# untitled.net
KiCad netlist of a schematic drawn in EAGLE
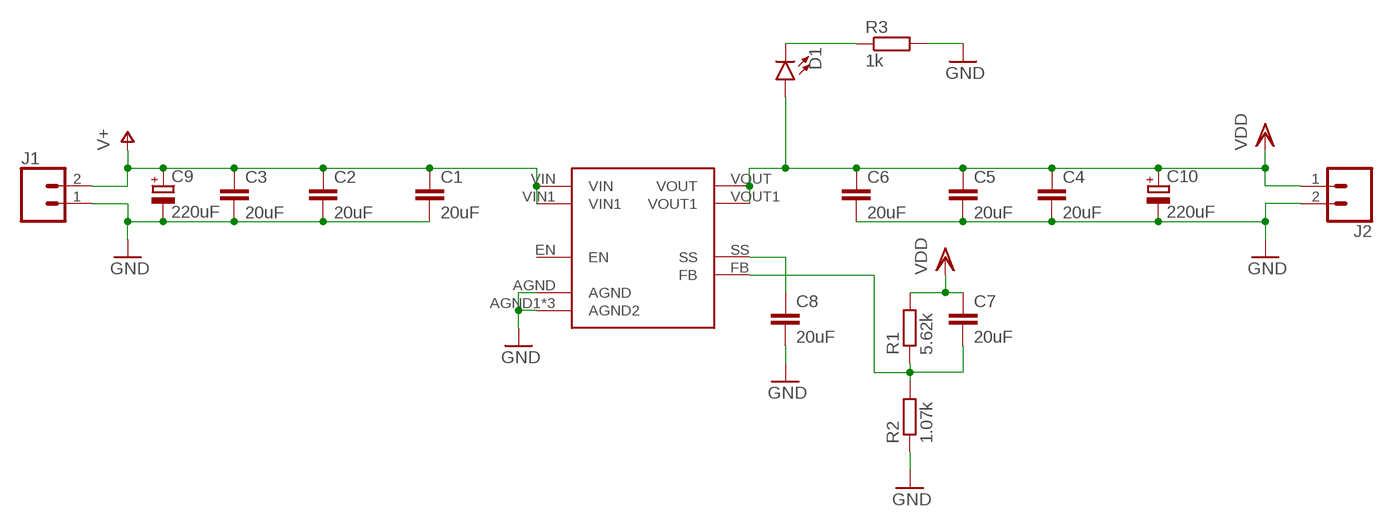
[diagram p0: schematic, sheet 1]

(export (version "E")
  (design (tool "Eeschema 10.0.6"))
  (components
    (comp (ref "C1")
      (value "20uF")
      (footprint "eagle-import:C0805K")
      (libsource (lib "eagle-import") (part "C-EUC0805K"))
    )
    (comp (ref "C2")
      (value "20uF")
      (footprint "eagle-import:C0805K")
      (libsource (lib "eagle-import") (part "C-EUC0805K"))
    )
    (comp (ref "C3")
      (value "20uF")
      (footprint "eagle-import:C0805K")
      (libsource (lib "eagle-import") (part "C-EUC0805K"))
    )
    (comp (ref "C4")
      (value "20uF")
      (footprint "eagle-import:C0805K")
      (libsource (lib "eagle-import") (part "C-EUC0805K"))
    )
    (comp (ref "C5")
      (value "20uF")
      (footprint "eagle-import:C0805K")
      (libsource (lib "eagle-import") (part "C-EUC0805K"))
    )
    (comp (ref "C6")
      (value "20uF")
      (footprint "eagle-import:C0805K")
      (libsource (lib "eagle-import") (part "C-EUC0805K"))
    )
    (comp (ref "C7")
      (value "20uF")
      (footprint "eagle-import:C0805K")
      (libsource (lib "eagle-import") (part "C-EUC0805K"))
    )
    (comp (ref "C8")
      (value "20uF")
      (footprint "eagle-import:C0805K")
      (libsource (lib "eagle-import") (part "C-EUC0805K"))
    )
    (comp (ref "C9")
      (value "220uF")
      (footprint "eagle-import:153CLV-0810")
      (libsource (lib "eagle-import") (part "CPOL-EU153CLV-0810"))
    )
    (comp (ref "C10")
      (value "220uF")
      (footprint "eagle-import:153CLV-0810")
      (libsource (lib "eagle-import") (part "CPOL-EU153CLV-0810"))
    )
    (comp (ref "D1")
      (value "LED5MM")
      (footprint "eagle-import:LED_5MM")
      (libsource (lib "eagle-import") (part "LED5MM"))
    )
    (comp (ref "J1")
      (value "CONN_025MM")
      (footprint "eagle-import:SCREWTERMINAL-5MM-2")
      (libsource (lib "eagle-import") (part "CONN_025MM"))
    )
    (comp (ref "J2")
      (value "CONN_025MM")
      (footprint "eagle-import:SCREWTERMINAL-5MM-2")
      (libsource (lib "eagle-import") (part "CONN_025MM"))
    )
    (comp (ref "R1")
      (value "5.62k")
      (footprint "eagle-import:R0805")
      (libsource (lib "eagle-import") (part "R-EU_R0805"))
    )
    (comp (ref "R2")
      (value "1.07k")
      (footprint "eagle-import:R0805")
      (libsource (lib "eagle-import") (part "R-EU_R0805"))
    )
    (comp (ref "R3")
      (value "1k")
      (footprint "eagle-import:R0805")
      (libsource (lib "eagle-import") (part "R-EU_R0805"))
    )
    (comp (ref "U$1")
      (value "LMZ13610")
      (footprint "eagle-import:LMZ13610")
      (libsource (lib "eagle-import") (part "LMZ13610"))
    )
  )
  (nets
    (net (code "1") (name "GND") (class "Default")
      (node (ref "C1") (pin "2") (pinfunction "2_2") (pintype "passive"))
      (node (ref "C10") (pin "-") (pinfunction "-_-") (pintype "passive"))
      (node (ref "C2") (pin "2") (pinfunction "2_2") (pintype "passive"))
      (node (ref "C3") (pin "2") (pinfunction "2_2") (pintype "passive"))
      (node (ref "C4") (pin "2") (pinfunction "2_2") (pintype "passive"))
      (node (ref "C5") (pin "2") (pinfunction "2_2") (pintype "passive"))
      (node (ref "C6") (pin "2") (pinfunction "2_2") (pintype "passive"))
      (node (ref "C8") (pin "2") (pinfunction "2_2") (pintype "passive"))
      (node (ref "C9") (pin "-") (pinfunction "-_-") (pintype "passive"))
      (node (ref "J1") (pin "1") (pinfunction "1_1") (pintype "passive"))
      (node (ref "J2") (pin "2") (pinfunction "2_2") (pintype "passive"))
      (node (ref "R2") (pin "1") (pinfunction "1_1") (pintype "passive"))
      (node (ref "R3") (pin "2") (pinfunction "2_2") (pintype "passive"))
      (node (ref "U$1") (pin "AGND") (pinfunction "AGND_AGND") (pintype "bidirectional"))
      (node (ref "U$1") (pin "AGND1") (pinfunction "AGND2_AGND1") (pintype "bidirectional"))
      (node (ref "U$1") (pin "AGND2") (pinfunction "AGND2_AGND2") (pintype "bidirectional"))
      (node (ref "U$1") (pin "AGND3") (pinfunction "AGND2_AGND3") (pintype "bidirectional"))
    )
    (net (code "2") (name "Net-(C7-Pad2)") (class "Default")
      (node (ref "C7") (pin "2") (pinfunction "2_2") (pintype "passive"))
      (node (ref "R1") (pin "1") (pinfunction "1_1") (pintype "passive"))
      (node (ref "R2") (pin "2") (pinfunction "2_2") (pintype "passive"))
      (node (ref "U$1") (pin "FB") (pinfunction "FB_FB") (pintype "bidirectional"))
    )
    (net (code "3") (name "Net-(C8-Pad1)") (class "Default")
      (node (ref "C8") (pin "1") (pinfunction "1_1") (pintype "passive"))
      (node (ref "U$1") (pin "SS") (pinfunction "SS_SS") (pintype "bidirectional"))
    )
    (net (code "4") (name "Net-(D1-C)") (class "Default")
      (node (ref "D1") (pin "K") (pinfunction "C_K") (pintype "passive"))
      (node (ref "R3") (pin "1") (pinfunction "1_1") (pintype "passive"))
    )
    (net (code "5") (name "V+") (class "Default")
      (node (ref "C1") (pin "1") (pinfunction "1_1") (pintype "passive"))
      (node (ref "C2") (pin "1") (pinfunction "1_1") (pintype "passive"))
      (node (ref "C3") (pin "1") (pinfunction "1_1") (pintype "passive"))
      (node (ref "C9") (pin "+") (pinfunction "+_+") (pintype "passive"))
      (node (ref "J1") (pin "2") (pinfunction "2_2") (pintype "passive"))
      (node (ref "U$1") (pin "VIN") (pinfunction "VIN_VIN") (pintype "bidirectional"))
      (node (ref "U$1") (pin "VIN1") (pinfunction "VIN1_VIN1") (pintype "bidirectional"))
    )
    (net (code "6") (name "VDD") (class "Default")
      (node (ref "C10") (pin "+") (pinfunction "+_+") (pintype "passive"))
      (node (ref "C4") (pin "1") (pinfunction "1_1") (pintype "passive"))
      (node (ref "C5") (pin "1") (pinfunction "1_1") (pintype "passive"))
      (node (ref "C6") (pin "1") (pinfunction "1_1") (pintype "passive"))
      (node (ref "C7") (pin "1") (pinfunction "1_1") (pintype "passive"))
      (node (ref "D1") (pin "A") (pinfunction "A_A") (pintype "passive"))
      (node (ref "J2") (pin "1") (pinfunction "1_1") (pintype "passive"))
      (node (ref "R1") (pin "2") (pinfunction "2_2") (pintype "passive"))
      (node (ref "U$1") (pin "VOUT") (pinfunction "VOUT_VOUT") (pintype "bidirectional"))
      (node (ref "U$1") (pin "VOUT1") (pinfunction "VOUT1_VOUT1") (pintype "bidirectional"))
    )
    (net (code "7") (name "unconnected-(U$1-PadEN)") (class "Default")
      (node (ref "U$1") (pin "EN") (pinfunction "EN_EN") (pintype "bidirectional"))
    )
  )
)
